# CO2SN_v2.net
KiCad netlist of a schematic drawn in EAGLE
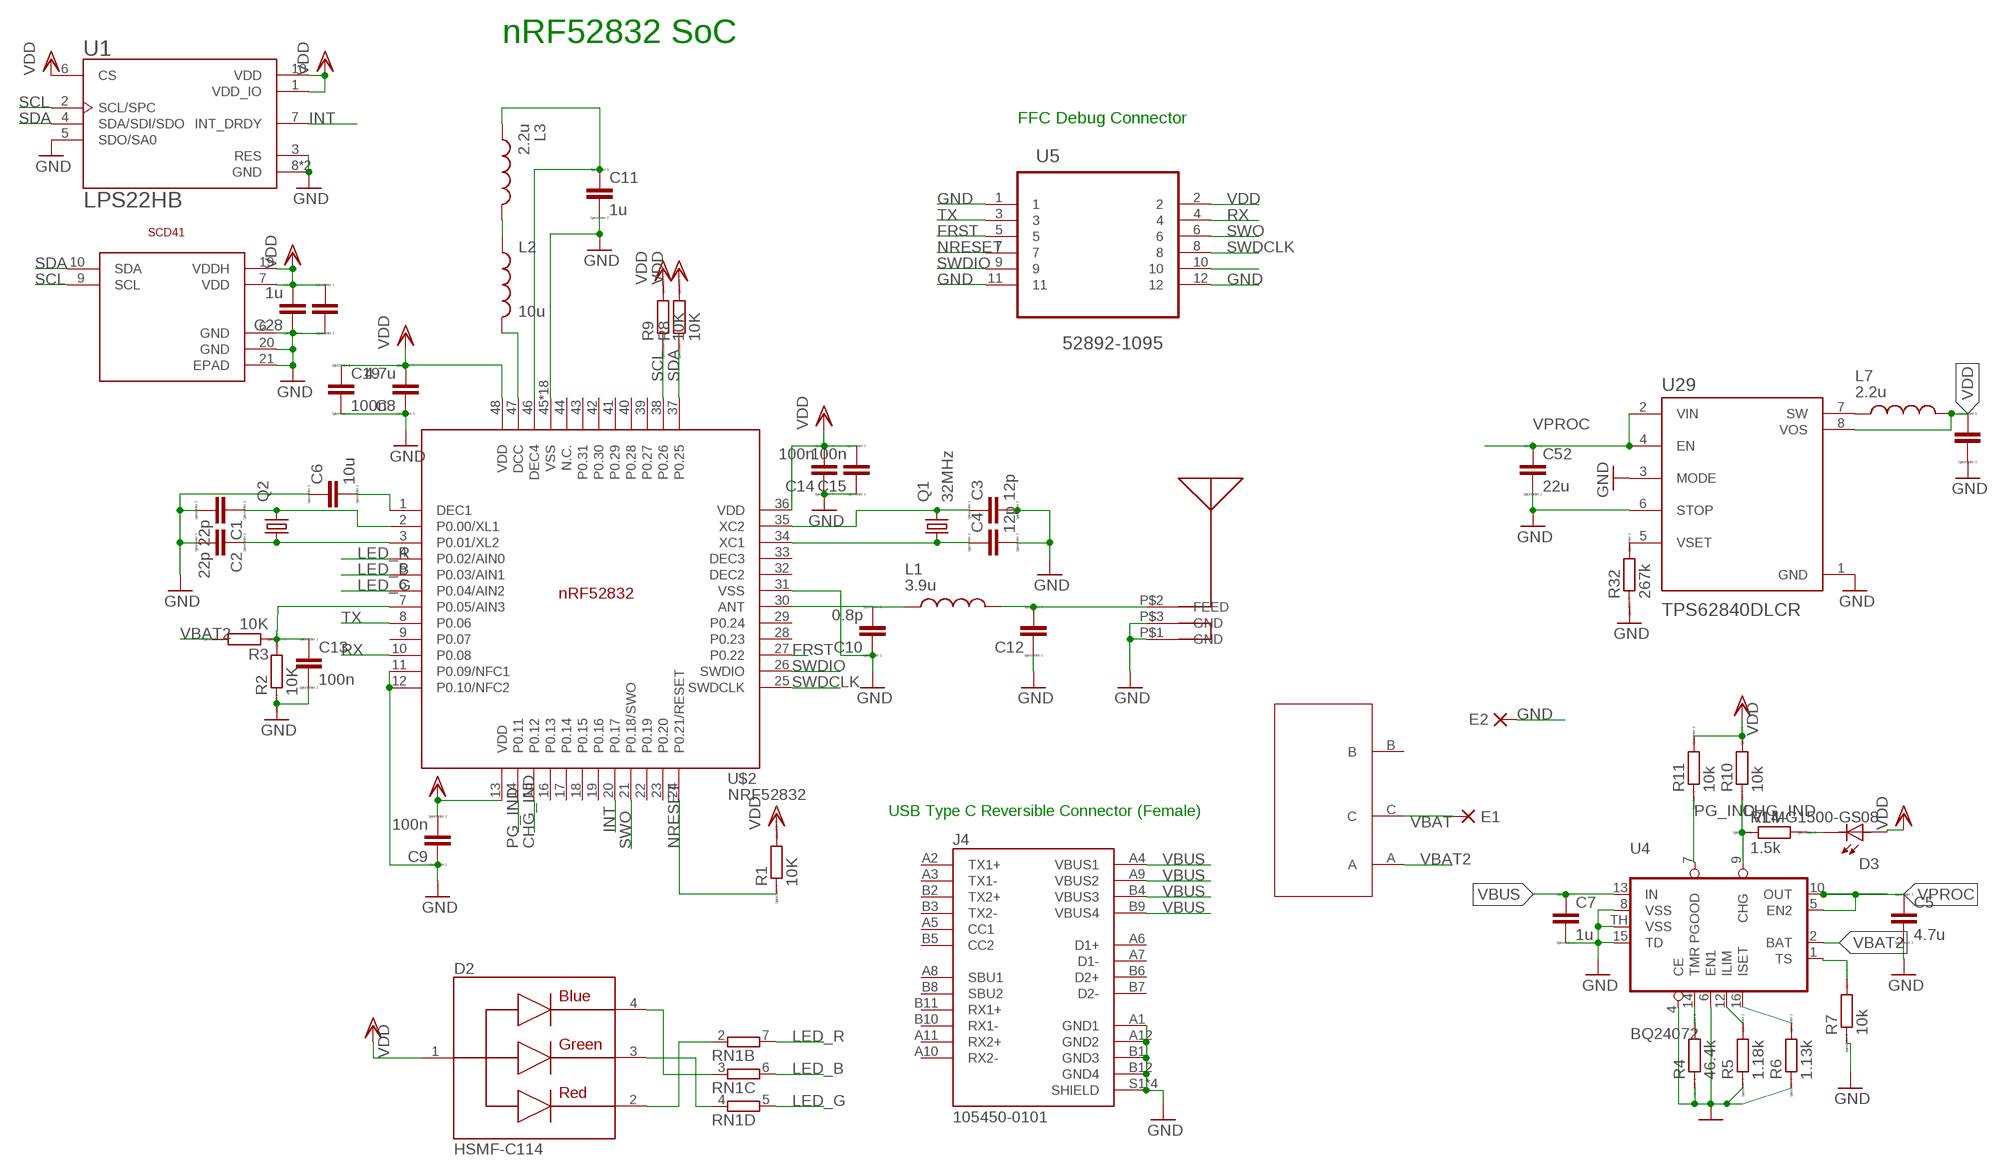
[diagram p0: schematic, sheet 1]

(export (version "E")
  (design (tool "Eeschema 10.0.6"))
  (components
    (comp (ref "C1")
      (value "22p")
      (footprint "eagle-import:C0402")
      (libsource (lib "eagle-import") (part "CC0402"))
    )
    (comp (ref "C2")
      (value "22p")
      (footprint "eagle-import:C0402")
      (libsource (lib "eagle-import") (part "CC0402"))
    )
    (comp (ref "C3")
      (value "12p")
      (footprint "eagle-import:C0402")
      (libsource (lib "eagle-import") (part "CC0402"))
    )
    (comp (ref "C4")
      (value "12p")
      (footprint "eagle-import:C0402")
      (libsource (lib "eagle-import") (part "CC0402"))
    )
    (comp (ref "C5")
      (value "4.7u")
      (footprint "eagle-import:C0402")
      (libsource (lib "eagle-import") (part "CC0402"))
    )
    (comp (ref "C6")
      (value "10u")
      (footprint "eagle-import:C0402")
      (libsource (lib "eagle-import") (part "CC0402"))
    )
    (comp (ref "C7")
      (value "1u")
      (footprint "eagle-import:C0402")
      (libsource (lib "eagle-import") (part "CC0402"))
    )
    (comp (ref "C8")
      (value "4.7u")
      (footprint "eagle-import:C0402")
      (libsource (lib "eagle-import") (part "CC0402"))
    )
    (comp (ref "C9")
      (value "100n")
      (footprint "eagle-import:C0603R")
      (libsource (lib "eagle-import") (part "CC0603R"))
    )
    (comp (ref "C10")
      (value "0.8p")
      (footprint "eagle-import:C0402")
      (libsource (lib "eagle-import") (part "CC0402"))
    )
    (comp (ref "C11")
      (value "1u")
      (footprint "eagle-import:C0402")
      (libsource (lib "eagle-import") (part "CC0402"))
    )
    (comp (ref "C12")
      (value "1.2p")
      (footprint "eagle-import:C0402")
      (libsource (lib "eagle-import") (part "CC0402"))
    )
    (comp (ref "C13")
      (value "100n")
      (footprint "eagle-import:C0402")
      (libsource (lib "eagle-import") (part "CC0402"))
    )
    (comp (ref "C14")
      (value "100n")
      (footprint "eagle-import:C0402")
      (libsource (lib "eagle-import") (part "CC0402"))
    )
    (comp (ref "C15")
      (value "100n")
      (footprint "eagle-import:C0402")
      (libsource (lib "eagle-import") (part "CC0402"))
    )
    (comp (ref "C19")
      (value "100n")
      (footprint "eagle-import:C0402")
      (libsource (lib "eagle-import") (part "CC0402"))
    )
    (comp (ref "C28")
      (value "1u")
      (footprint "eagle-import:C0402")
      (libsource (lib "eagle-import") (part "CC0402"))
    )
    (comp (ref "C29")
      (value "22u")
      (footprint "eagle-import:C0603R")
      (libsource (lib "eagle-import") (part "CC0603R"))
    )
    (comp (ref "C52")
      (value "22u")
      (footprint "eagle-import:C0603R")
      (libsource (lib "eagle-import") (part "CC0603R"))
    )
    (comp (ref "C58")
      (value "22u")
      (footprint "eagle-import:C0603R")
      (libsource (lib "eagle-import") (part "CC0603R"))
    )
    (comp (ref "D2")
      (value "HSMF-C114")
      (footprint "eagle-import:DIOSC160X150X35-4N")
      (fields (field (name "MF") "Broadcom Limited"))
      (libsource (lib "eagle-import") (part "HSMF-C114"))
    )
    (comp (ref "D3")
      (value "VLMG1500-GS08")
      (footprint "eagle-import:LEDC1005X35N")
      (fields (field (name "MF") "Vishay"))
      (libsource (lib "eagle-import") (part "VLMG1500-GS08"))
    )
    (comp (ref "E1")
      (value "DPADS_PAD-0400-S")
      (footprint "eagle-import:DPADS_0400-S")
      (libsource (lib "eagle-import") (part "DPADS_PAD-0400-S"))
    )
    (comp (ref "E2")
      (value "DPADS_PAD-0400-S")
      (footprint "eagle-import:DPADS_0400-S")
      (libsource (lib "eagle-import") (part "DPADS_PAD-0400-S"))
    )
    (comp (ref "J4")
      (value "105450-0101")
      (footprint "eagle-import:MOLEX_105450-0101")
      (fields (field (name "MF") "Molex") (field (name "MP") "1054500101"))
      (libsource (lib "eagle-import") (part "105450-0101"))
    )
    (comp (ref "L1")
      (value "3.9u")
      (footprint "eagle-import:INDC0402X26N")
      (fields (field (name "MF") "TDK") (field (name "MP") "MHQ0402P7N5JT000"))
      (libsource (lib "eagle-import") (part "MHQ0402P7N5JT000"))
    )
    (comp (ref "L2")
      (value "10u")
      (footprint "eagle-import:L0603")
      (libsource (lib "eagle-import") (part "INDUCTOR"))
    )
    (comp (ref "L3")
      (value "2.2u")
      (footprint "eagle-import:INDC0402X26N")
      (fields (field (name "MF") "TDK") (field (name "MP") "MHQ0402P7N5JT000"))
      (libsource (lib "eagle-import") (part "MHQ0402P7N5JT000"))
    )
    (comp (ref "L7")
      (value "2.2u")
      (footprint "eagle-import:INDC3225X120N")
      (fields (field (name "MF") "Murata") (field (name "MP") "1277AS-H-1R5M=P2"))
      (libsource (lib "eagle-import") (part "1277AS-H-1R5M=P2"))
    )
    (comp (ref "Q1")
      (value "32MHz")
      (footprint "eagle-import:2.0X1.6_KX-5")
      (libsource (lib "eagle-import") (part "KX-5"))
    )
    (comp (ref "Q2")
      (value "KX-327-RT")
      (footprint "eagle-import:2.0X1.2")
      (libsource (lib "eagle-import") (part "KX-327-RT"))
    )
    (comp (ref "R1")
      (value "10K")
      (footprint "eagle-import:R0402")
      (libsource (lib "eagle-import") (part "RR0402"))
    )
    (comp (ref "R2")
      (value "10K")
      (footprint "eagle-import:R0402")
      (libsource (lib "eagle-import") (part "RR0402"))
    )
    (comp (ref "R3")
      (value "10K")
      (footprint "eagle-import:R0402")
      (libsource (lib "eagle-import") (part "RR0402"))
    )
    (comp (ref "R4")
      (value "46.4k")
      (footprint "eagle-import:R0402")
      (libsource (lib "eagle-import") (part "RR0402"))
    )
    (comp (ref "R5")
      (value "1.18k")
      (footprint "eagle-import:R0402")
      (libsource (lib "eagle-import") (part "RR0402"))
    )
    (comp (ref "R6")
      (value "1.13k")
      (footprint "eagle-import:R0402")
      (libsource (lib "eagle-import") (part "RR0402"))
    )
    (comp (ref "R7")
      (value "10k")
      (footprint "eagle-import:R0402")
      (libsource (lib "eagle-import") (part "RR0402"))
    )
    (comp (ref "R8")
      (value "10K")
      (footprint "eagle-import:R0402")
      (libsource (lib "eagle-import") (part "RR0402"))
    )
    (comp (ref "R9")
      (value "10K")
      (footprint "eagle-import:R0402")
      (libsource (lib "eagle-import") (part "RR0402"))
    )
    (comp (ref "R10")
      (value "10k")
      (footprint "eagle-import:R0402")
      (libsource (lib "eagle-import") (part "RR0402"))
    )
    (comp (ref "R11")
      (value "10k")
      (footprint "eagle-import:R0402")
      (libsource (lib "eagle-import") (part "RR0402"))
    )
    (comp (ref "R14")
      (value "1.5k")
      (footprint "eagle-import:R0402")
      (libsource (lib "eagle-import") (part "RR0402"))
    )
    (comp (ref "R32")
      (value "267k")
      (footprint "eagle-import:R0402")
      (libsource (lib "eagle-import") (part "RR0402"))
    )
    (comp (ref "RN1")
      (value "4R-N0402ARV341")
      (footprint "eagle-import:4X0402ARV341")
      (libsource (lib "eagle-import") (part "4R-N0402ARV341"))
    )
    (comp (ref "U$1")
      (value "SCD41")
      (footprint "eagle-import:SCD41")
      (libsource (lib "eagle-import") (part "SCD41"))
    )
    (comp (ref "U$2")
      (value "NRF52832")
      (footprint "eagle-import:QFN40P600X600X90-48_N")
      (libsource (lib "eagle-import") (part "NRF52832"))
    )
    (comp (ref "U$3")
      (value "SMDTOGGLESWITCH")
      (footprint "eagle-import:SMDTOGGLESWITCH")
      (libsource (lib "eagle-import") (part "SMDTOGGLESWITCH"))
    )
    (comp (ref "U$4")
      (value "CHIPANTENNAL2")
      (footprint "eagle-import:CHIPANTENNAL2")
      (libsource (lib "eagle-import") (part "CHIPANTENNAL2"))
    )
    (comp (ref "U1")
      (value "LPS22HB")
      (footprint "eagle-import:LGA10R50P2X3_200X200X80")
      (fields (field (name "MF") "STMicroelectronics"))
      (libsource (lib "eagle-import") (part "LPS22HB"))
    )
    (comp (ref "U4")
      (value "BQ24072")
      (footprint "eagle-import:S-PVQFN-N16")
      (libsource (lib "eagle-import") (part "BQ24072"))
    )
    (comp (ref "U5")
      (value "52892-1095")
      (footprint "eagle-import:MOLEX_52892-1095")
      (fields (field (name "MF") "Molex"))
      (libsource (lib "eagle-import") (part "52892-1095"))
    )
    (comp (ref "U29")
      (value "TPS62840DLCR")
      (footprint "eagle-import:SON50P200X150X100-8N")
      (fields (field (name "MF") "Texas Instruments"))
      (libsource (lib "eagle-import") (part "TPS62840DLCR"))
    )
  )
  (nets
    (net (code "1") (name "/CHG_IND") (class "Default")
      (node (ref "R10") (pin "1") (pinfunction "1_1") (pintype "passive"))
      (node (ref "R14") (pin "1") (pinfunction "1_1") (pintype "passive"))
      (node (ref "U$2") (pin "15") (pinfunction "P0.12_15") (pintype "bidirectional"))
      (node (ref "U4") (pin "9") (pinfunction "CHG_9") (pintype "bidirectional"))
    )
    (net (code "2") (name "/FRST") (class "Default")
      (node (ref "U$2") (pin "27") (pinfunction "P0.22_27") (pintype "bidirectional"))
      (node (ref "U5") (pin "5") (pinfunction "5_5") (pintype "passive"))
    )
    (net (code "3") (name "/INT") (class "Default")
      (node (ref "U$2") (pin "20") (pinfunction "P0.17_20") (pintype "bidirectional"))
      (node (ref "U1") (pin "7") (pinfunction "INT_DRDY_7") (pintype "output"))
    )
    (net (code "4") (name "/LED_B") (class "Default")
      (node (ref "RN1") (pin "6") (pinfunction "2_6") (pintype "passive"))
      (node (ref "U$2") (pin "5") (pinfunction "P0.03/AIN1_5") (pintype "bidirectional"))
    )
    (net (code "5") (name "/LED_G") (class "Default")
      (node (ref "RN1") (pin "5") (pinfunction "2_5") (pintype "passive"))
      (node (ref "U$2") (pin "6") (pinfunction "P0.04/AIN2_6") (pintype "bidirectional"))
    )
    (net (code "6") (name "/LED_R") (class "Default")
      (node (ref "RN1") (pin "7") (pinfunction "2_7") (pintype "passive"))
      (node (ref "U$2") (pin "4") (pinfunction "P0.02/AIN0_4") (pintype "bidirectional"))
    )
    (net (code "7") (name "/NRESET") (class "Default")
      (node (ref "R1") (pin "1") (pinfunction "1_1") (pintype "passive"))
      (node (ref "U$2") (pin "24") (pinfunction "P0.21/RESET_24") (pintype "bidirectional"))
      (node (ref "U5") (pin "7") (pinfunction "7_7") (pintype "passive"))
    )
    (net (code "8") (name "/PG_IND") (class "Default")
      (node (ref "R11") (pin "1") (pinfunction "1_1") (pintype "passive"))
      (node (ref "U$2") (pin "14") (pinfunction "P0.11_14") (pintype "bidirectional"))
      (node (ref "U4") (pin "7") (pinfunction "PGOOD_7") (pintype "bidirectional"))
    )
    (net (code "9") (name "/RX") (class "Default")
      (node (ref "U$2") (pin "10") (pinfunction "P0.08_10") (pintype "bidirectional"))
      (node (ref "U5") (pin "4") (pinfunction "4_4") (pintype "passive"))
    )
    (net (code "10") (name "/SCL") (class "Default")
      (node (ref "R9") (pin "1") (pinfunction "1_1") (pintype "passive"))
      (node (ref "U$1") (pin "9") (pinfunction "SCL_9") (pintype "bidirectional"))
      (node (ref "U$2") (pin "38") (pinfunction "P0.26_38") (pintype "bidirectional"))
      (node (ref "U1") (pin "2") (pinfunction "SCL/SPC_2") (pintype "input"))
    )
    (net (code "11") (name "/SDA") (class "Default")
      (node (ref "R8") (pin "1") (pinfunction "1_1") (pintype "passive"))
      (node (ref "U$1") (pin "10") (pinfunction "SDA_10") (pintype "bidirectional"))
      (node (ref "U$2") (pin "37") (pinfunction "P0.25_37") (pintype "bidirectional"))
      (node (ref "U1") (pin "4") (pinfunction "SDA/SDI/SDO_4") (pintype "bidirectional"))
    )
    (net (code "12") (name "/SWDCLK") (class "Default")
      (node (ref "U$2") (pin "25") (pinfunction "SWDCLK_25") (pintype "input"))
      (node (ref "U5") (pin "8") (pinfunction "8_8") (pintype "passive"))
    )
    (net (code "13") (name "/SWDIO") (class "Default")
      (node (ref "U$2") (pin "26") (pinfunction "SWDIO_26") (pintype "bidirectional"))
      (node (ref "U5") (pin "9") (pinfunction "9_9") (pintype "passive"))
    )
    (net (code "14") (name "/SWO") (class "Default")
      (node (ref "U$2") (pin "21") (pinfunction "P0.18/SWO_21") (pintype "bidirectional"))
      (node (ref "U5") (pin "6") (pinfunction "6_6") (pintype "passive"))
    )
    (net (code "15") (name "/TX") (class "Default")
      (node (ref "U$2") (pin "8") (pinfunction "P0.06_8") (pintype "bidirectional"))
      (node (ref "U5") (pin "3") (pinfunction "3_3") (pintype "passive"))
    )
    (net (code "16") (name "/VBAT") (class "Default")
      (node (ref "E1") (pin "PAD") (pinfunction "P_PAD") (pintype "passive"))
      (node (ref "U$3") (pin "C") (pinfunction "C_C") (pintype "bidirectional"))
    )
    (net (code "17") (name "GND") (class "Default")
      (node (ref "C1") (pin "2") (pinfunction "2_2") (pintype "passive"))
      (node (ref "C10") (pin "1") (pinfunction "1_1") (pintype "passive"))
      (node (ref "C11") (pin "2") (pinfunction "2_2") (pintype "passive"))
      (node (ref "C12") (pin "1") (pinfunction "1_1") (pintype "passive"))
      (node (ref "C13") (pin "2") (pinfunction "2_2") (pintype "passive"))
      (node (ref "C14") (pin "1") (pinfunction "1_1") (pintype "passive"))
      (node (ref "C15") (pin "1") (pinfunction "1_1") (pintype "passive"))
      (node (ref "C19") (pin "2") (pinfunction "2_2") (pintype "passive"))
      (node (ref "C2") (pin "2") (pinfunction "2_2") (pintype "passive"))
      (node (ref "C28") (pin "1") (pinfunction "1_1") (pintype "passive"))
      (node (ref "C29") (pin "2") (pinfunction "2_2") (pintype "passive"))
      (node (ref "C3") (pin "2") (pinfunction "2_2") (pintype "passive"))
      (node (ref "C4") (pin "2") (pinfunction "2_2") (pintype "passive"))
      (node (ref "C5") (pin "2") (pinfunction "2_2") (pintype "passive"))
      (node (ref "C52") (pin "2") (pinfunction "2_2") (pintype "passive"))
      (node (ref "C58") (pin "2") (pinfunction "2_2") (pintype "passive"))
      (node (ref "C6") (pin "1") (pinfunction "1_1") (pintype "passive"))
      (node (ref "C7") (pin "2") (pinfunction "2_2") (pintype "passive"))
      (node (ref "C8") (pin "1") (pinfunction "1_1") (pintype "passive"))
      (node (ref "C9") (pin "1") (pinfunction "1_1") (pintype "passive"))
      (node (ref "E2") (pin "PAD") (pinfunction "P_PAD") (pintype "passive"))
      (node (ref "J4") (pin "A1") (pinfunction "GND1_A1") (pintype "passive"))
      (node (ref "J4") (pin "A12") (pinfunction "GND2_A12") (pintype "passive"))
      (node (ref "J4") (pin "B1") (pinfunction "GND3_B1") (pintype "passive"))
      (node (ref "J4") (pin "B12") (pinfunction "GND4_B12") (pintype "passive"))
      (node (ref "J4") (pin "S1") (pinfunction "SHIELD_S1") (pintype "passive"))
      (node (ref "J4") (pin "S2") (pinfunction "SHIELD_S2") (pintype "passive"))
      (node (ref "J4") (pin "S3") (pinfunction "SHIELD_S3") (pintype "passive"))
      (node (ref "J4") (pin "S4") (pinfunction "SHIELD_S4") (pintype "passive"))
      (node (ref "R2") (pin "1") (pinfunction "1_1") (pintype "passive"))
      (node (ref "R32") (pin "1") (pinfunction "1_1") (pintype "passive"))
      (node (ref "R4") (pin "1") (pinfunction "1_1") (pintype "passive"))
      (node (ref "R5") (pin "1") (pinfunction "1_1") (pintype "passive"))
      (node (ref "R6") (pin "1") (pinfunction "1_1") (pintype "passive"))
      (node (ref "R7") (pin "1") (pinfunction "1_1") (pintype "passive"))
      (node (ref "U$1") (pin "20") (pinfunction "GND_20") (pintype "bidirectional"))
      (node (ref "U$1") (pin "21") (pinfunction "EPAD_21") (pintype "bidirectional"))
      (node (ref "U$1") (pin "6") (pinfunction "GND_6") (pintype "bidirectional"))
      (node (ref "U$2") (pin "11") (pinfunction "P0.09/NFC1_11") (pintype "bidirectional"))
      (node (ref "U$2") (pin "12") (pinfunction "P0.10/NFC2_12") (pintype "bidirectional"))
      (node (ref "U$2") (pin "31") (pinfunction "VSS_31") (pintype "bidirectional"))
      (node (ref "U$2") (pin "45") (pinfunction "VSS_45") (pintype "power_in"))
      (node (ref "U$2") (pin "PAD") (pinfunction "VSS_PAD") (pintype "power_in"))
      (node (ref "U$2") (pin "PAD@VIA01") (pinfunction "VSS_PAD@VIA01") (pintype "power_in"))
      (node (ref "U$2") (pin "PAD@VIA02") (pinfunction "VSS_PAD@VIA02") (pintype "power_in"))
      (node (ref "U$2") (pin "PAD@VIA03") (pinfunction "VSS_PAD@VIA03") (pintype "power_in"))
      (node (ref "U$2") (pin "PAD@VIA04") (pinfunction "VSS_PAD@VIA04") (pintype "power_in"))
      (node (ref "U$2") (pin "PAD@VIA05") (pinfunction "VSS_PAD@VIA05") (pintype "power_in"))
      (node (ref "U$2") (pin "PAD@VIA06") (pinfunction "VSS_PAD@VIA06") (pintype "power_in"))
      (node (ref "U$2") (pin "PAD@VIA07") (pinfunction "VSS_PAD@VIA07") (pintype "power_in"))
      (node (ref "U$2") (pin "PAD@VIA08") (pinfunction "VSS_PAD@VIA08") (pintype "power_in"))
      (node (ref "U$2") (pin "PAD@VIA09") (pinfunction "VSS_PAD@VIA09") (pintype "power_in"))
      (node (ref "U$2") (pin "PAD@VIA10") (pinfunction "VSS_PAD@VIA10") (pintype "power_in"))
      (node (ref "U$2") (pin "PAD@VIA11") (pinfunction "VSS_PAD@VIA11") (pintype "power_in"))
      (node (ref "U$2") (pin "PAD@VIA12") (pinfunction "VSS_PAD@VIA12") (pintype "power_in"))
      (node (ref "U$2") (pin "PAD@VIA13") (pinfunction "VSS_PAD@VIA13") (pintype "power_in"))
      (node (ref "U$2") (pin "PAD@VIA14") (pinfunction "VSS_PAD@VIA14") (pintype "power_in"))
      (node (ref "U$2") (pin "PAD@VIA15") (pinfunction "VSS_PAD@VIA15") (pintype "power_in"))
      (node (ref "U$2") (pin "PAD@VIA16") (pinfunction "VSS_PAD@VIA16") (pintype "power_in"))
      (node (ref "U$4") (pin "P$1") (pinfunction "GND_P$1") (pintype "bidirectional"))
      (node (ref "U$4") (pin "P$3") (pinfunction "GND_P$3") (pintype "bidirectional"))
      (node (ref "U1") (pin "3") (pinfunction "RES_3") (pintype "power_in"))
      (node (ref "U1") (pin "5") (pinfunction "SDO/SA0_5") (pintype "bidirectional"))
      (node (ref "U1") (pin "8") (pinfunction "GND_8") (pintype "power_in"))
      (node (ref "U1") (pin "9") (pinfunction "GND_9") (pintype "power_in"))
      (node (ref "U29") (pin "1") (pinfunction "GND_1") (pintype "power_in"))
      (node (ref "U29") (pin "3") (pinfunction "MODE_3") (pintype "input"))
      (node (ref "U29") (pin "6") (pinfunction "STOP_6") (pintype "input"))
      (node (ref "U4") (pin "15") (pinfunction "TD_15") (pintype "bidirectional"))
      (node (ref "U4") (pin "4") (pinfunction "CE_4") (pintype "bidirectional"))
      (node (ref "U4") (pin "6") (pinfunction "EN1_6") (pintype "bidirectional"))
      (node (ref "U4") (pin "8") (pinfunction "VSS_8") (pintype "power_in"))
      (node (ref "U4") (pin "TH") (pinfunction "VSS_TH") (pintype "power_in"))
      (node (ref "U5") (pin "1") (pinfunction "1_1") (pintype "passive"))
      (node (ref "U5") (pin "11") (pinfunction "11_11") (pintype "passive"))
      (node (ref "U5") (pin "12") (pinfunction "12_12") (pintype "passive"))
    )
    (net (code "18") (name "Net-(D3-Pad2)") (class "Default")
      (node (ref "D3") (pin "2") (pinfunction "2_2") (pintype "passive"))
      (node (ref "R14") (pin "2") (pinfunction "2_2") (pintype "passive"))
    )
    (net (code "19") (name "Net-(L2-Pad1)") (class "Default")
      (node (ref "L2") (pin "1") (pinfunction "1_1") (pintype "passive"))
      (node (ref "L3") (pin "2") (pinfunction "2_2") (pintype "passive"))
    )
    (net (code "20") (name "Net-(Q1-2)") (class "Default")
      (node (ref "C3") (pin "1") (pinfunction "1_1") (pintype "passive"))
      (node (ref "Q1") (pin "3") (pinfunction "2_3") (pintype "passive"))
      (node (ref "U$2") (pin "35") (pinfunction "XC2_35") (pintype "output"))
    )
    (net (code "21") (name "Net-(RN1B-1)") (class "Default")
      (node (ref "D2") (pin "2") (pinfunction "2_2") (pintype "passive"))
      (node (ref "RN1") (pin "2") (pinfunction "1_2") (pintype "passive"))
    )
    (net (code "22") (name "Net-(RN1C-1)") (class "Default")
      (node (ref "D2") (pin "4") (pinfunction "4_4") (pintype "passive"))
      (node (ref "RN1") (pin "3") (pinfunction "1_3") (pintype "passive"))
    )
    (net (code "23") (name "Net-(RN1D-1)") (class "Default")
      (node (ref "D2") (pin "3") (pinfunction "3_3") (pintype "passive"))
      (node (ref "RN1") (pin "4") (pinfunction "1_4") (pintype "passive"))
    )
    (net (code "24") (name "Net-(U$2-ANT)") (class "Default")
      (node (ref "C10") (pin "2") (pinfunction "2_2") (pintype "passive"))
      (node (ref "L1") (pin "1") (pinfunction "1_1") (pintype "passive"))
      (node (ref "U$2") (pin "30") (pinfunction "ANT_30") (pintype "bidirectional"))
    )
    (net (code "25") (name "Net-(U$2-DCC)") (class "Default")
      (node (ref "L2") (pin "2") (pinfunction "2_2") (pintype "passive"))
      (node (ref "U$2") (pin "47") (pinfunction "DCC_47") (pintype "output"))
    )
    (net (code "26") (name "Net-(U$2-DEC1)") (class "Default")
      (node (ref "C6") (pin "2") (pinfunction "2_2") (pintype "passive"))
      (node (ref "U$2") (pin "1") (pinfunction "DEC1_1") (pintype "power_in"))
    )
    (net (code "27") (name "Net-(U$2-DEC4)") (class "Default")
      (node (ref "C11") (pin "1") (pinfunction "1_1") (pintype "passive"))
      (node (ref "L3") (pin "1") (pinfunction "1_1") (pintype "passive"))
      (node (ref "U$2") (pin "46") (pinfunction "DEC4_46") (pintype "power_in"))
    )
    (net (code "28") (name "Net-(U$2-P0.00{slash}XL1)") (class "Default")
      (node (ref "C1") (pin "1") (pinfunction "1_1") (pintype "passive"))
      (node (ref "Q2") (pin "2") (pinfunction "2_2") (pintype "passive"))
      (node (ref "U$2") (pin "2") (pinfunction "P0.00/XL1_2") (pintype "bidirectional"))
    )
    (net (code "29") (name "Net-(U$2-P0.01{slash}XL2)") (class "Default")
      (node (ref "C2") (pin "1") (pinfunction "1_1") (pintype "passive"))
      (node (ref "Q2") (pin "1") (pinfunction "1_1") (pintype "passive"))
      (node (ref "U$2") (pin "3") (pinfunction "P0.01/XL2_3") (pintype "bidirectional"))
    )
    (net (code "30") (name "Net-(U$2-P0.05{slash}AIN3)") (class "Default")
      (node (ref "C13") (pin "1") (pinfunction "1_1") (pintype "passive"))
      (node (ref "R2") (pin "2") (pinfunction "2_2") (pintype "passive"))
      (node (ref "R3") (pin "1") (pinfunction "1_1") (pintype "passive"))
      (node (ref "U$2") (pin "7") (pinfunction "P0.05/AIN3_7") (pintype "bidirectional"))
    )
    (net (code "31") (name "Net-(U$2-XC1)") (class "Default")
      (node (ref "C4") (pin "1") (pinfunction "1_1") (pintype "passive"))
      (node (ref "Q1") (pin "1") (pinfunction "1_1") (pintype "passive"))
      (node (ref "U$2") (pin "34") (pinfunction "XC1_34") (pintype "input"))
    )
    (net (code "32") (name "Net-(U$4-FEED)") (class "Default")
      (node (ref "C12") (pin "2") (pinfunction "2_2") (pintype "passive"))
      (node (ref "L1") (pin "2") (pinfunction "2_2") (pintype "passive"))
      (node (ref "U$4") (pin "P$2") (pinfunction "FEED_P$2") (pintype "bidirectional"))
    )
    (net (code "33") (name "Net-(U4-ILIM)") (class "Default")
      (node (ref "R5") (pin "2") (pinfunction "2_2") (pintype "passive"))
      (node (ref "U4") (pin "12") (pinfunction "ILIM_12") (pintype "bidirectional"))
    )
    (net (code "34") (name "Net-(U4-ISET)") (class "Default")
      (node (ref "R6") (pin "2") (pinfunction "2_2") (pintype "passive"))
      (node (ref "U4") (pin "16") (pinfunction "ISET_16") (pintype "input"))
    )
    (net (code "35") (name "Net-(U4-TMR)") (class "Default")
      (node (ref "R4") (pin "2") (pinfunction "2_2") (pintype "passive"))
      (node (ref "U4") (pin "14") (pinfunction "TMR_14") (pintype "bidirectional"))
    )
    (net (code "36") (name "Net-(U4-TS)") (class "Default")
      (node (ref "R7") (pin "2") (pinfunction "2_2") (pintype "passive"))
      (node (ref "U4") (pin "1") (pinfunction "TS_1") (pintype "input"))
    )
    (net (code "37") (name "Net-(U29-SW)") (class "Default")
      (node (ref "L7") (pin "1") (pinfunction "1_1") (pintype "passive"))
      (node (ref "U29") (pin "7") (pinfunction "SW_7") (pintype "power_in"))
    )
    (net (code "38") (name "Net-(U29-VSET)") (class "Default")
      (node (ref "R32") (pin "2") (pinfunction "2_2") (pintype "passive"))
      (node (ref "U29") (pin "5") (pinfunction "VSET_5") (pintype "input"))
    )
    (net (code "39") (name "VBAT2") (class "Default")
      (node (ref "R3") (pin "2") (pinfunction "2_2") (pintype "passive"))
      (node (ref "U$3") (pin "A") (pinfunction "A_A") (pintype "bidirectional"))
      (node (ref "U4") (pin "2") (pinfunction "BAT_2") (pintype "input"))
    )
    (net (code "40") (name "VBUS") (class "Default")
      (node (ref "C7") (pin "1") (pinfunction "1_1") (pintype "passive"))
      (node (ref "J4") (pin "A4") (pinfunction "VBUS1_A4") (pintype "passive"))
      (node (ref "J4") (pin "A9") (pinfunction "VBUS2_A9") (pintype "passive"))
      (node (ref "J4") (pin "B4") (pinfunction "VBUS3_B4") (pintype "passive"))
      (node (ref "J4") (pin "B9") (pinfunction "VBUS4_B9") (pintype "passive"))
      (node (ref "U4") (pin "13") (pinfunction "IN_13") (pintype "input"))
    )
    (net (code "41") (name "VDD") (class "Default")
      (node (ref "C14") (pin "2") (pinfunction "2_2") (pintype "passive"))
      (node (ref "C15") (pin "2") (pinfunction "2_2") (pintype "passive"))
      (node (ref "C19") (pin "1") (pinfunction "1_1") (pintype "passive"))
      (node (ref "C28") (pin "2") (pinfunction "2_2") (pintype "passive"))
      (node (ref "C29") (pin "1") (pinfunction "1_1") (pintype "passive"))
      (node (ref "C58") (pin "1") (pinfunction "1_1") (pintype "passive"))
      (node (ref "C8") (pin "2") (pinfunction "2_2") (pintype "passive"))
      (node (ref "C9") (pin "2") (pinfunction "2_2") (pintype "passive"))
      (node (ref "D2") (pin "1") (pinfunction "1_1") (pintype "passive"))
      (node (ref "D3") (pin "1") (pinfunction "1_1") (pintype "passive"))
      (node (ref "L7") (pin "2") (pinfunction "2_2") (pintype "passive"))
      (node (ref "R1") (pin "2") (pinfunction "2_2") (pintype "passive"))
      (node (ref "R10") (pin "2") (pinfunction "2_2") (pintype "passive"))
      (node (ref "R11") (pin "2") (pinfunction "2_2") (pintype "passive"))
      (node (ref "R8") (pin "2") (pinfunction "2_2") (pintype "passive"))
      (node (ref "R9") (pin "2") (pinfunction "2_2") (pintype "passive"))
      (node (ref "U$1") (pin "19") (pinfunction "VDDH_19") (pintype "bidirectional"))
      (node (ref "U$1") (pin "7") (pinfunction "VDD_7") (pintype "bidirectional"))
      (node (ref "U$2") (pin "13") (pinfunction "VDD_13") (pintype "power_in"))
      (node (ref "U$2") (pin "36") (pinfunction "VDD_36") (pintype "power_in"))
      (node (ref "U$2") (pin "48") (pinfunction "VDD_48") (pintype "power_in"))
      (node (ref "U1") (pin "1") (pinfunction "VDD_IO_1") (pintype "power_in"))
      (node (ref "U1") (pin "10") (pinfunction "VDD_10") (pintype "power_in"))
      (node (ref "U1") (pin "6") (pinfunction "CS_6") (pintype "input"))
      (node (ref "U29") (pin "8") (pinfunction "VOS_8") (pintype "input"))
      (node (ref "U5") (pin "2") (pinfunction "2_2") (pintype "passive"))
    )
    (net (code "42") (name "VPROC") (class "Default")
      (node (ref "C5") (pin "1") (pinfunction "1_1") (pintype "passive"))
      (node (ref "C52") (pin "1") (pinfunction "1_1") (pintype "passive"))
      (node (ref "U29") (pin "2") (pinfunction "VIN_2") (pintype "power_in"))
      (node (ref "U29") (pin "4") (pinfunction "EN_4") (pintype "input"))
      (node (ref "U4") (pin "10") (pinfunction "OUT_10") (pintype "output"))
      (node (ref "U4") (pin "5") (pinfunction "EN2_5") (pintype "input"))
    )
    (net (code "43") (name "unconnected-(J4-CC1-PadA5)") (class "Default")
      (node (ref "J4") (pin "A5") (pinfunction "CC1_A5") (pintype "passive"))
    )
    (net (code "44") (name "unconnected-(J4-CC2-PadB5)") (class "Default")
      (node (ref "J4") (pin "B5") (pinfunction "CC2_B5") (pintype "passive"))
    )
    (net (code "45") (name "unconnected-(J4-D1+-PadA6)") (class "Default")
      (node (ref "J4") (pin "A6") (pinfunction "D1+_A6") (pintype "passive"))
    )
    (net (code "46") (name "unconnected-(J4-D1--PadA7)") (class "Default")
      (node (ref "J4") (pin "A7") (pinfunction "D1-_A7") (pintype "passive"))
    )
    (net (code "47") (name "unconnected-(J4-D2+-PadB6)") (class "Default")
      (node (ref "J4") (pin "B6") (pinfunction "D2+_B6") (pintype "passive"))
    )
    (net (code "48") (name "unconnected-(J4-D2--PadB7)") (class "Default")
      (node (ref "J4") (pin "B7") (pinfunction "D2-_B7") (pintype "passive"))
    )
    (net (code "49") (name "unconnected-(J4-RX1+-PadB11)") (class "Default")
      (node (ref "J4") (pin "B11") (pinfunction "RX1+_B11") (pintype "passive"))
    )
    (net (code "50") (name "unconnected-(J4-RX1--PadB10)") (class "Default")
      (node (ref "J4") (pin "B10") (pinfunction "RX1-_B10") (pintype "passive"))
    )
    (net (code "51") (name "unconnected-(J4-RX2+-PadA11)") (class "Default")
      (node (ref "J4") (pin "A11") (pinfunction "RX2+_A11") (pintype "passive"))
    )
    (net (code "52") (name "unconnected-(J4-RX2--PadA10)") (class "Default")
      (node (ref "J4") (pin "A10") (pinfunction "RX2-_A10") (pintype "passive"))
    )
    (net (code "53") (name "unconnected-(J4-SBU1-PadA8)") (class "Default")
      (node (ref "J4") (pin "A8") (pinfunction "SBU1_A8") (pintype "passive"))
    )
    (net (code "54") (name "unconnected-(J4-SBU2-PadB8)") (class "Default")
      (node (ref "J4") (pin "B8") (pinfunction "SBU2_B8") (pintype "passive"))
    )
    (net (code "55") (name "unconnected-(J4-TX1+-PadA2)") (class "Default")
      (node (ref "J4") (pin "A2") (pinfunction "TX1+_A2") (pintype "passive"))
    )
    (net (code "56") (name "unconnected-(J4-TX1--PadA3)") (class "Default")
      (node (ref "J4") (pin "A3") (pinfunction "TX1-_A3") (pintype "passive"))
    )
    (net (code "57") (name "unconnected-(J4-TX2+-PadB2)") (class "Default")
      (node (ref "J4") (pin "B2") (pinfunction "TX2+_B2") (pintype "passive"))
    )
    (net (code "58") (name "unconnected-(J4-TX2--PadB3)") (class "Default")
      (node (ref "J4") (pin "B3") (pinfunction "TX2-_B3") (pintype "passive"))
    )
    (net (code "59") (name "unconnected-(U$2-DEC2-Pad32)") (class "Default")
      (node (ref "U$2") (pin "32") (pinfunction "DEC2_32") (pintype "bidirectional"))
    )
    (net (code "60") (name "unconnected-(U$2-DEC3-Pad33)") (class "Default")
      (node (ref "U$2") (pin "33") (pinfunction "DEC3_33") (pintype "bidirectional"))
    )
    (net (code "61") (name "unconnected-(U$2-N.C.-Pad44)") (class "Default")
      (node (ref "U$2") (pin "44") (pinfunction "N.C._44") (pintype "no_connect"))
    )
    (net (code "62") (name "unconnected-(U$2-P0.07-Pad9)") (class "Default")
      (node (ref "U$2") (pin "9") (pinfunction "P0.07_9") (pintype "bidirectional"))
    )
    (net (code "63") (name "unconnected-(U$2-P0.13-Pad16)") (class "Default")
      (node (ref "U$2") (pin "16") (pinfunction "P0.13_16") (pintype "bidirectional"))
    )
    (net (code "64") (name "unconnected-(U$2-P0.14-Pad17)") (class "Default")
      (node (ref "U$2") (pin "17") (pinfunction "P0.14_17") (pintype "bidirectional"))
    )
    (net (code "65") (name "unconnected-(U$2-P0.15-Pad18)") (class "Default")
      (node (ref "U$2") (pin "18") (pinfunction "P0.15_18") (pintype "bidirectional"))
    )
    (net (code "66") (name "unconnected-(U$2-P0.16-Pad19)") (class "Default")
      (node (ref "U$2") (pin "19") (pinfunction "P0.16_19") (pintype "bidirectional"))
    )
    (net (code "67") (name "unconnected-(U$2-P0.19-Pad22)") (class "Default")
      (node (ref "U$2") (pin "22") (pinfunction "P0.19_22") (pintype "bidirectional"))
    )
    (net (code "68") (name "unconnected-(U$2-P0.20-Pad23)") (class "Default")
      (node (ref "U$2") (pin "23") (pinfunction "P0.20_23") (pintype "bidirectional"))
    )
    (net (code "69") (name "unconnected-(U$2-P0.23-Pad28)") (class "Default")
      (node (ref "U$2") (pin "28") (pinfunction "P0.23_28") (pintype "bidirectional"))
    )
    (net (code "70") (name "unconnected-(U$2-P0.24-Pad29)") (class "Default")
      (node (ref "U$2") (pin "29") (pinfunction "P0.24_29") (pintype "bidirectional"))
    )
    (net (code "71") (name "unconnected-(U$2-P0.27-Pad39)") (class "Default")
      (node (ref "U$2") (pin "39") (pinfunction "P0.27_39") (pintype "bidirectional"))
    )
    (net (code "72") (name "unconnected-(U$2-P0.28-Pad40)") (class "Default")
      (node (ref "U$2") (pin "40") (pinfunction "P0.28_40") (pintype "bidirectional"))
    )
    (net (code "73") (name "unconnected-(U$2-P0.29-Pad41)") (class "Default")
      (node (ref "U$2") (pin "41") (pinfunction "P0.29_41") (pintype "bidirectional"))
    )
    (net (code "74") (name "unconnected-(U$2-P0.30-Pad42)") (class "Default")
      (node (ref "U$2") (pin "42") (pinfunction "P0.30_42") (pintype "bidirectional"))
    )
    (net (code "75") (name "unconnected-(U$2-P0.31-Pad43)") (class "Default")
      (node (ref "U$2") (pin "43") (pinfunction "P0.31_43") (pintype "bidirectional"))
    )
    (net (code "76") (name "unconnected-(U$3-PadB)") (class "Default")
      (node (ref "U$3") (pin "B") (pinfunction "B_B") (pintype "bidirectional"))
    )
    (net (code "77") (name "unconnected-(U5-Pad10)") (class "Default")
      (node (ref "U5") (pin "10") (pinfunction "10_10") (pintype "passive"))
    )
  )
)
